# BlancerCarMicrocontrollers.net
KiCad netlist of a schematic drawn in Altium Designer
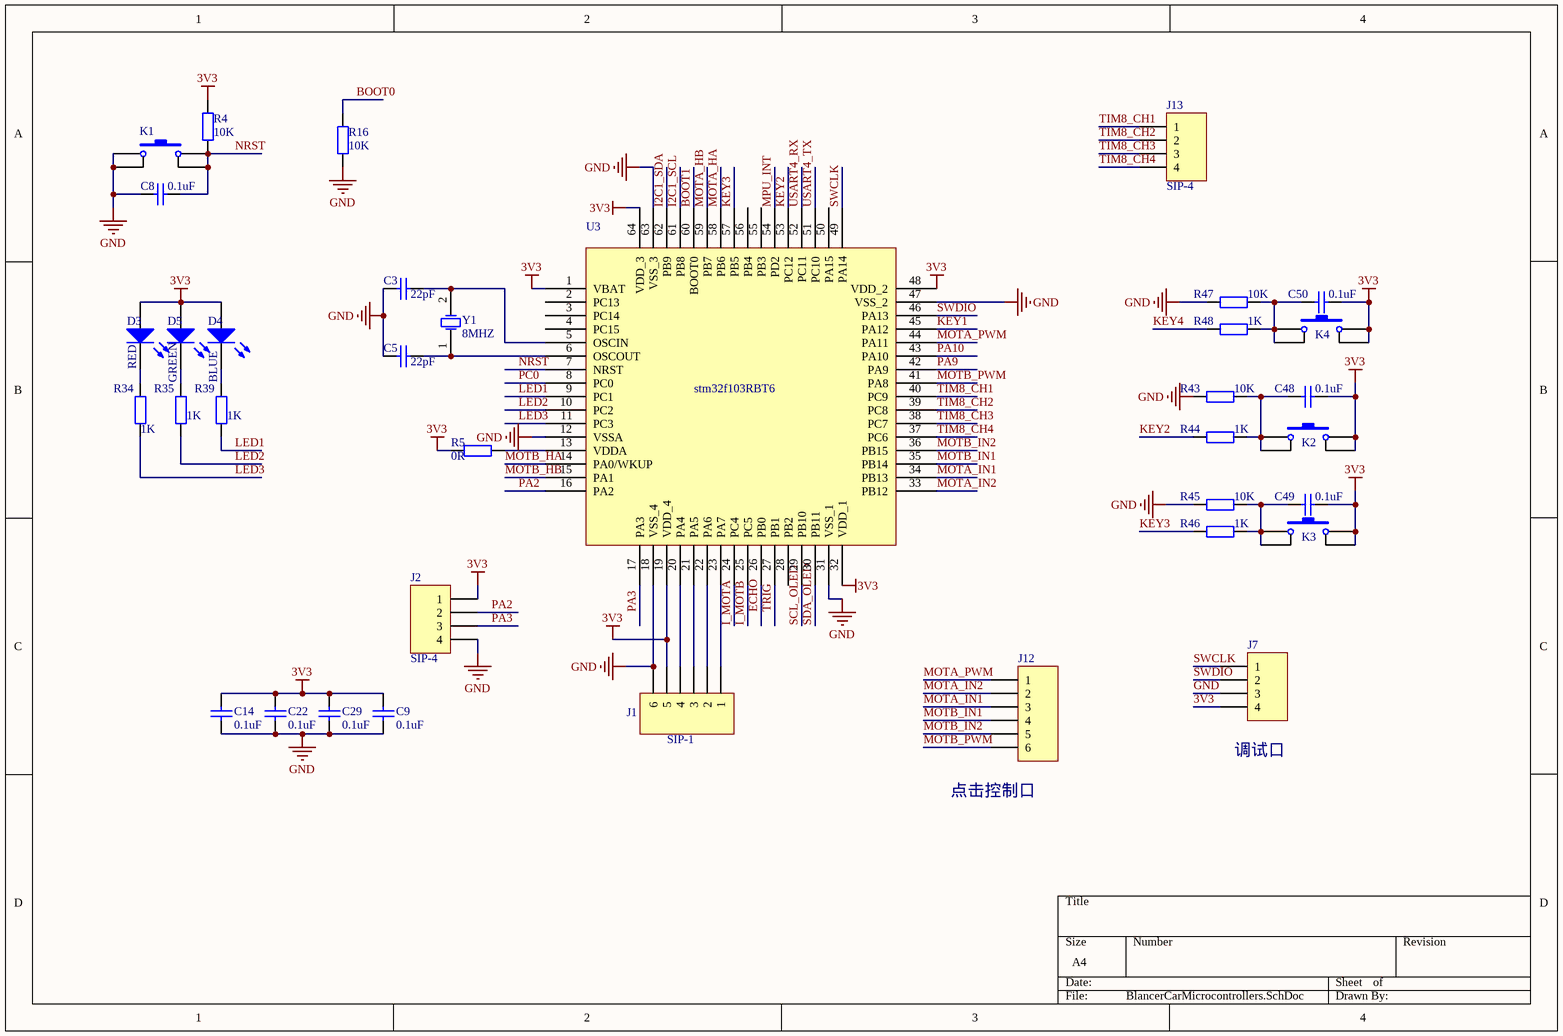
[diagram p0: BlancerCarMicrocontrollers.SchDoc]

(export (version "E")
  (design (tool "Eeschema 10.0.6"))
  (components
    (comp (ref "C3")
      (value "22pF")
      (footprint "0805-1")
      (description "Capacitor")
      (fields (field (name "Comment") "Cap") (field (name "PUBLISHER") "Altium Limited"))
      (libsource (lib "BlancerCar") (part "Cap"))
    )
    (comp (ref "C5")
      (value "22pF")
      (footprint "0805-1")
      (description "Capacitor")
      (fields (field (name "Comment") "Cap") (field (name "PUBLISHER") "Altium Limited"))
      (libsource (lib "BlancerCar") (part "Cap"))
    )
    (comp (ref "C8")
      (value "0.1uF")
      (footprint "0805-1")
      (description "Capacitor")
      (fields (field (name "Comment") "Cap") (field (name "PUBLISHER") "Altium Limited"))
      (libsource (lib "BlancerCar") (part "Cap"))
    )
    (comp (ref "C9")
      (value "0.1uF")
      (footprint "0805-1")
      (description "Capacitor")
      (fields (field (name "Comment") "Cap") (field (name "PUBLISHER") "Altium Limited"))
      (libsource (lib "BlancerCar") (part "Cap"))
    )
    (comp (ref "C14")
      (value "0.1uF")
      (footprint "0805-1")
      (description "Capacitor")
      (fields (field (name "Comment") "Cap") (field (name "PUBLISHER") "Altium Limited"))
      (libsource (lib "BlancerCar") (part "Cap"))
    )
    (comp (ref "C22")
      (value "0.1uF")
      (footprint "0805-1")
      (description "Capacitor")
      (fields (field (name "Comment") "Cap") (field (name "PUBLISHER") "Altium Limited"))
      (libsource (lib "BlancerCar") (part "Cap"))
    )
    (comp (ref "C29")
      (value "0.1uF")
      (footprint "0805-1")
      (description "Capacitor")
      (fields (field (name "Comment") "Cap") (field (name "PUBLISHER") "Altium Limited"))
      (libsource (lib "BlancerCar") (part "Cap"))
    )
    (comp (ref "C48")
      (value "0.1uF")
      (footprint "0805-1")
      (description "Capacitor")
      (fields (field (name "Comment") "Cap") (field (name "PUBLISHER") "Altium Limited"))
      (libsource (lib "BlancerCar") (part "Cap"))
    )
    (comp (ref "C49")
      (value "0.1uF")
      (footprint "0805-1")
      (description "Capacitor")
      (fields (field (name "Comment") "Cap") (field (name "PUBLISHER") "Altium Limited"))
      (libsource (lib "BlancerCar") (part "Cap"))
    )
    (comp (ref "C50")
      (value "0.1uF")
      (footprint "0805-1")
      (description "Capacitor")
      (fields (field (name "Comment") "Cap") (field (name "PUBLISHER") "Altium Limited"))
      (libsource (lib "BlancerCar") (part "Cap"))
    )
    (comp (ref "D3")
      (value "RED")
      (footprint "LED_0805")
      (description "发光二极管")
      (fields (field (name "PUBLISHER") "Altium Limited"))
      (libsource (lib "xdhADL") (part "LED0"))
    )
    (comp (ref "D4")
      (value "BLUE")
      (footprint "LED_0805")
      (description "发光二极管")
      (fields (field (name "PUBLISHER") "Altium Limited"))
      (libsource (lib "xdhADL") (part "LED0"))
    )
    (comp (ref "D5")
      (value "GREEN")
      (footprint "LED_0805")
      (description "发光二极管")
      (fields (field (name "PUBLISHER") "Altium Limited"))
      (libsource (lib "xdhADL") (part "LED0"))
    )
    (comp (ref "J1")
      (value "SIP-1")
      (footprint "HDR1X6")
      (description "Header, 6-Pin")
      (fields (field (name "PUBLISHER") "Altium Limited"))
      (libsource (lib "Miscellaneous Connectors") (part "Header 6"))
    )
    (comp (ref "J2")
      (value "SIP-4")
      (footprint "HDR1X4")
      (description "Header, 4-Pin")
      (fields (field (name "PUBLISHER") "Altium Limited"))
      (libsource (lib "BlancerCar") (part "Header 4"))
    )
    (comp (ref "J7")
      (value "Header 4")
      (footprint "HDR1X4")
      (description "Header, 4-Pin")
      (fields (field (name "PUBLISHER") "Altium Limited"))
      (libsource (lib "Miscellaneous Connectors") (part "Header 4"))
    )
    (comp (ref "J12")
      (value "Header 6")
      (footprint "HDR1X6")
      (description "Header, 6-Pin")
      (fields (field (name "PUBLISHER") "Altium Limited"))
      (libsource (lib "") (part "Header 6_1"))
    )
    (comp (ref "J13")
      (value "SIP-4")
      (footprint "HDR1X4")
      (description "Header, 4-Pin")
      (fields (field (name "PUBLISHER") "Altium Limited"))
      (libsource (lib "Miscellaneous Connectors") (part "Header 4"))
    )
    (comp (ref "K1")
      (value "SW-PB4")
      (footprint "SW_PB4_A1")
      (description "微动开关")
      (fields (field (name "PUBLISHER") "Altium Limited"))
      (libsource (lib "xdhADL") (part "SW-PB4"))
    )
    (comp (ref "K2")
      (value "SW-PB4")
      (footprint "SW_PB4_A1")
      (description "微动开关")
      (fields (field (name "PUBLISHER") "Altium Limited"))
      (libsource (lib "xdhADL") (part "SW-PB4"))
    )
    (comp (ref "K3")
      (value "SW-PB4")
      (footprint "SW_PB4_A1")
      (description "微动开关")
      (fields (field (name "PUBLISHER") "Altium Limited"))
      (libsource (lib "xdhADL") (part "SW-PB4"))
    )
    (comp (ref "K4")
      (value "SW-PB4")
      (footprint "SW_PB4_A1")
      (description "微动开关")
      (fields (field (name "PUBLISHER") "Altium Limited"))
      (libsource (lib "xdhADL") (part "SW-PB4"))
    )
    (comp (ref "R4")
      (value "10K")
      (footprint "0805-1")
      (description "贴片电阻")
      (fields (field (name "Comment") "Res1") (field (name "PUBLISHER") "Altium Limited"))
      (libsource (lib "") (part "Res1_2"))
    )
    (comp (ref "R5")
      (value "0R")
      (footprint "0805-1")
      (description "贴片电阻")
      (fields (field (name "Comment") "Res1") (field (name "PUBLISHER") "Altium Limited"))
      (libsource (lib "") (part "Res1_1"))
    )
    (comp (ref "R16")
      (value "10K")
      (footprint "0805-1")
      (description "贴片电阻")
      (fields (field (name "Comment") "Res1") (field (name "PUBLISHER") "Altium Limited"))
      (libsource (lib "xdhADL") (part "Res1"))
    )
    (comp (ref "R34")
      (value "1K")
      (footprint "0805-1")
      (description "贴片电阻")
      (fields (field (name "Comment") "Res1") (field (name "PUBLISHER") "Altium Limited"))
      (libsource (lib "xdhADL") (part "Res1"))
    )
    (comp (ref "R35")
      (value "1K")
      (footprint "0805-1")
      (description "贴片电阻")
      (fields (field (name "Comment") "Res1") (field (name "PUBLISHER") "Altium Limited"))
      (libsource (lib "xdhADL") (part "Res1"))
    )
    (comp (ref "R39")
      (value "1K")
      (footprint "0805-1")
      (description "贴片电阻")
      (fields (field (name "Comment") "Res1") (field (name "PUBLISHER") "Altium Limited"))
      (libsource (lib "xdhADL") (part "Res1"))
    )
    (comp (ref "R43")
      (value "10K")
      (footprint "0805-1")
      (description "贴片电阻")
      (fields (field (name "Comment") "Res1") (field (name "PUBLISHER") "Altium Limited"))
      (libsource (lib "") (part "Res1_1"))
    )
    (comp (ref "R44")
      (value "1K")
      (footprint "0805-1")
      (description "贴片电阻")
      (fields (field (name "Comment") "Res1") (field (name "PUBLISHER") "Altium Limited"))
      (libsource (lib "") (part "Res1_1"))
    )
    (comp (ref "R45")
      (value "10K")
      (footprint "0805-1")
      (description "贴片电阻")
      (fields (field (name "Comment") "Res1") (field (name "PUBLISHER") "Altium Limited"))
      (libsource (lib "") (part "Res1_1"))
    )
    (comp (ref "R46")
      (value "1K")
      (footprint "0805-1")
      (description "贴片电阻")
      (fields (field (name "Comment") "Res1") (field (name "PUBLISHER") "Altium Limited"))
      (libsource (lib "") (part "Res1_1"))
    )
    (comp (ref "R47")
      (value "10K")
      (footprint "0805-1")
      (description "贴片电阻")
      (fields (field (name "Comment") "Res1") (field (name "PUBLISHER") "Altium Limited"))
      (libsource (lib "") (part "Res1_1"))
    )
    (comp (ref "R48")
      (value "1K")
      (footprint "0805-1")
      (description "贴片电阻")
      (fields (field (name "Comment") "Res1") (field (name "PUBLISHER") "Altium Limited"))
      (libsource (lib "") (part "Res1_1"))
    )
    (comp (ref "U3")
      (value "stm32f103RBT6")
      (footprint "STM32F103RBT6(LQFP-64)")
      (libsource (lib "xdhADL") (part "stm32f103RBT6"))
    )
    (comp (ref "Y1")
      (value "8MHZ")
      (footprint "晶振 8M")
      (description "Crystal Oscillator")
      (fields (field (name "PUBLISHER") "Altium Limited"))
      (libsource (lib "BlancerCar") (part "XTAL"))
    )
  )
  (nets
    (net (code "1") (name "/BOOT0") (class "Default")
      (node (ref "R16") (pin "2") (pinfunction "2_2") (pintype "passive"))
    )
    (net (code "2") (name "/BOOT1") (class "Default")
      (node (ref "U3") (pin "60") (pinfunction "BOOT0_60") (pintype "passive"))
    )
    (net (code "3") (name "/ECHO") (class "Default")
      (node (ref "U3") (pin "26") (pinfunction "PB0_26") (pintype "passive"))
    )
    (net (code "4") (name "/I2C1_SCL") (class "Default")
      (node (ref "U3") (pin "61") (pinfunction "PB8_61") (pintype "passive"))
    )
    (net (code "5") (name "/I2C1_SDA") (class "Default")
      (node (ref "U3") (pin "62") (pinfunction "PB9_62") (pintype "passive"))
    )
    (net (code "6") (name "/I_MOTA") (class "Default")
      (node (ref "U3") (pin "24") (pinfunction "PC4_24") (pintype "passive"))
    )
    (net (code "7") (name "/I_MOTB") (class "Default")
      (node (ref "U3") (pin "25") (pinfunction "PC5_25") (pintype "passive"))
    )
    (net (code "8") (name "/KEY1") (class "Default")
      (node (ref "U3") (pin "45") (pinfunction "PA12_45") (pintype "passive"))
    )
    (net (code "9") (name "/KEY2") (class "Default")
      (node (ref "R44") (pin "1") (pinfunction "1_1") (pintype "passive"))
      (node (ref "U3") (pin "53") (pinfunction "PC12_53") (pintype "passive"))
    )
    (net (code "10") (name "/KEY3") (class "Default")
      (node (ref "R46") (pin "1") (pinfunction "1_1") (pintype "passive"))
      (node (ref "U3") (pin "57") (pinfunction "PB5_57") (pintype "passive"))
    )
    (net (code "11") (name "/KEY4") (class "Default")
      (node (ref "R48") (pin "1") (pinfunction "1_1") (pintype "passive"))
    )
    (net (code "12") (name "/LED1") (class "Default")
      (node (ref "R39") (pin "1") (pinfunction "1_1") (pintype "passive"))
      (node (ref "U3") (pin "9") (pinfunction "PC1_9") (pintype "passive"))
    )
    (net (code "13") (name "/LED2") (class "Default")
      (node (ref "R35") (pin "1") (pinfunction "1_1") (pintype "passive"))
      (node (ref "U3") (pin "10") (pinfunction "PC2_10") (pintype "passive"))
    )
    (net (code "14") (name "/LED3") (class "Default")
      (node (ref "R34") (pin "1") (pinfunction "1_1") (pintype "passive"))
      (node (ref "U3") (pin "11") (pinfunction "PC3_11") (pintype "passive"))
    )
    (net (code "15") (name "/MOTA_HA") (class "Default")
      (node (ref "U3") (pin "58") (pinfunction "PB6_58") (pintype "passive"))
    )
    (net (code "16") (name "/MOTA_HB") (class "Default")
      (node (ref "U3") (pin "59") (pinfunction "PB7_59") (pintype "passive"))
    )
    (net (code "17") (name "/MOTA_IN1") (class "Default")
      (node (ref "J12") (pin "3") (pinfunction "3_3") (pintype "passive"))
      (node (ref "U3") (pin "34") (pinfunction "PB13_34") (pintype "passive"))
    )
    (net (code "18") (name "/MOTA_IN2") (class "Default")
      (node (ref "J12") (pin "2") (pinfunction "2_2") (pintype "passive"))
      (node (ref "U3") (pin "33") (pinfunction "PB12_33") (pintype "passive"))
    )
    (net (code "19") (name "/MOTA_PWM") (class "Default")
      (node (ref "J12") (pin "1") (pinfunction "1_1") (pintype "passive"))
      (node (ref "U3") (pin "44") (pinfunction "PA11_44") (pintype "passive"))
    )
    (net (code "20") (name "/MOTB_HA") (class "Default")
      (node (ref "U3") (pin "14") (pinfunction "PA0/WKUP_14") (pintype "passive"))
    )
    (net (code "21") (name "/MOTB_HB") (class "Default")
      (node (ref "U3") (pin "15") (pinfunction "PA1_15") (pintype "passive"))
    )
    (net (code "22") (name "/MOTB_IN1") (class "Default")
      (node (ref "J12") (pin "4") (pinfunction "4_4") (pintype "passive"))
      (node (ref "U3") (pin "35") (pinfunction "PB14_35") (pintype "passive"))
    )
    (net (code "23") (name "/MOTB_IN2") (class "Default")
      (node (ref "J12") (pin "5") (pinfunction "5_5") (pintype "passive"))
      (node (ref "U3") (pin "36") (pinfunction "PB15_36") (pintype "passive"))
    )
    (net (code "24") (name "/MOTB_PWM") (class "Default")
      (node (ref "J12") (pin "6") (pinfunction "6_6") (pintype "passive"))
      (node (ref "U3") (pin "41") (pinfunction "PA8_41") (pintype "passive"))
    )
    (net (code "25") (name "/MPU_INT") (class "Default")
      (node (ref "U3") (pin "54") (pinfunction "PD2_54") (pintype "passive"))
    )
    (net (code "26") (name "/NRST") (class "Default")
      (node (ref "C8") (pin "2") (pinfunction "2_2") (pintype "passive"))
      (node (ref "K1") (pin "2") (pinfunction "2_2") (pintype "passive"))
      (node (ref "K1") (pin "3") (pinfunction "3_3") (pintype "passive"))
      (node (ref "R4") (pin "2") (pinfunction "2_2") (pintype "passive"))
      (node (ref "U3") (pin "7") (pinfunction "NRST_7") (pintype "passive"))
    )
    (net (code "27") (name "/PA2") (class "Default")
      (node (ref "J2") (pin "2") (pinfunction "2_2") (pintype "passive"))
      (node (ref "U3") (pin "16") (pinfunction "PA2_16") (pintype "passive"))
    )
    (net (code "28") (name "/PA3") (class "Default")
      (node (ref "J2") (pin "3") (pinfunction "3_3") (pintype "passive"))
      (node (ref "U3") (pin "17") (pinfunction "PA3_17") (pintype "passive"))
    )
    (net (code "29") (name "/PA9") (class "Default")
      (node (ref "U3") (pin "42") (pinfunction "PA9_42") (pintype "passive"))
    )
    (net (code "30") (name "/PA10") (class "Default")
      (node (ref "U3") (pin "43") (pinfunction "PA10_43") (pintype "passive"))
    )
    (net (code "31") (name "/PC0") (class "Default")
      (node (ref "U3") (pin "8") (pinfunction "PC0_8") (pintype "passive"))
    )
    (net (code "32") (name "/SCL_OLED") (class "Default")
      (node (ref "U3") (pin "29") (pinfunction "PB10_29") (pintype "passive"))
    )
    (net (code "33") (name "/SDA_OLED") (class "Default")
      (node (ref "U3") (pin "30") (pinfunction "PB11_30") (pintype "passive"))
    )
    (net (code "34") (name "/SWCLK") (class "Default")
      (node (ref "J7") (pin "1") (pinfunction "1_1") (pintype "passive"))
      (node (ref "U3") (pin "49") (pinfunction "PA14_49") (pintype "passive"))
    )
    (net (code "35") (name "/SWDIO") (class "Default")
      (node (ref "J7") (pin "2") (pinfunction "2_2") (pintype "passive"))
      (node (ref "U3") (pin "46") (pinfunction "PA13_46") (pintype "passive"))
    )
    (net (code "36") (name "/TIM8_CH1") (class "Default")
      (node (ref "J13") (pin "1") (pinfunction "1_1") (pintype "passive"))
      (node (ref "U3") (pin "40") (pinfunction "PC9_40") (pintype "passive"))
    )
    (net (code "37") (name "/TIM8_CH2") (class "Default")
      (node (ref "J13") (pin "2") (pinfunction "2_2") (pintype "passive"))
      (node (ref "U3") (pin "39") (pinfunction "PC8_39") (pintype "passive"))
    )
    (net (code "38") (name "/TIM8_CH3") (class "Default")
      (node (ref "J13") (pin "3") (pinfunction "3_3") (pintype "passive"))
      (node (ref "U3") (pin "38") (pinfunction "PC7_38") (pintype "passive"))
    )
    (net (code "39") (name "/TIM8_CH4") (class "Default")
      (node (ref "J13") (pin "4") (pinfunction "4_4") (pintype "passive"))
      (node (ref "U3") (pin "37") (pinfunction "PC6_37") (pintype "passive"))
    )
    (net (code "40") (name "/TRIG") (class "Default")
      (node (ref "U3") (pin "27") (pinfunction "PB1_27") (pintype "passive"))
    )
    (net (code "41") (name "/USART4_RX") (class "Default")
      (node (ref "U3") (pin "52") (pinfunction "PC11_52") (pintype "passive"))
    )
    (net (code "42") (name "/USART4_TX") (class "Default")
      (node (ref "U3") (pin "51") (pinfunction "PC10_51") (pintype "passive"))
    )
    (net (code "43") (name "3V3") (class "Default")
      (node (ref "C14") (pin "2") (pinfunction "2_2") (pintype "passive"))
      (node (ref "C22") (pin "2") (pinfunction "2_2") (pintype "passive"))
      (node (ref "C29") (pin "2") (pinfunction "2_2") (pintype "passive"))
      (node (ref "C48") (pin "2") (pinfunction "2_2") (pintype "passive"))
      (node (ref "C49") (pin "2") (pinfunction "2_2") (pintype "passive"))
      (node (ref "C50") (pin "2") (pinfunction "2_2") (pintype "passive"))
      (node (ref "C9") (pin "2") (pinfunction "2_2") (pintype "passive"))
      (node (ref "D3") (pin "1") (pinfunction "A_1") (pintype "passive"))
      (node (ref "D4") (pin "1") (pinfunction "A_1") (pintype "passive"))
      (node (ref "D5") (pin "1") (pinfunction "A_1") (pintype "passive"))
      (node (ref "J1") (pin "5") (pinfunction "5_5") (pintype "passive"))
      (node (ref "J2") (pin "1") (pinfunction "1_1") (pintype "passive"))
      (node (ref "J7") (pin "4") (pinfunction "4_4") (pintype "passive"))
      (node (ref "K2") (pin "2") (pinfunction "2_2") (pintype "passive"))
      (node (ref "K2") (pin "3") (pinfunction "3_3") (pintype "passive"))
      (node (ref "K3") (pin "2") (pinfunction "2_2") (pintype "passive"))
      (node (ref "K3") (pin "3") (pinfunction "3_3") (pintype "passive"))
      (node (ref "K4") (pin "2") (pinfunction "2_2") (pintype "passive"))
      (node (ref "K4") (pin "3") (pinfunction "3_3") (pintype "passive"))
      (node (ref "R4") (pin "1") (pinfunction "1_1") (pintype "passive"))
      (node (ref "R5") (pin "1") (pinfunction "1_1") (pintype "passive"))
      (node (ref "U3") (pin "1") (pinfunction "VBAT_1") (pintype "passive"))
      (node (ref "U3") (pin "19") (pinfunction "VDD_4_19") (pintype "passive"))
      (node (ref "U3") (pin "32") (pinfunction "VDD_1_32") (pintype "passive"))
      (node (ref "U3") (pin "48") (pinfunction "VDD_2_48") (pintype "passive"))
      (node (ref "U3") (pin "64") (pinfunction "VDD_3_64") (pintype "passive"))
    )
    (net (code "44") (name "GND") (class "Default")
      (node (ref "C14") (pin "1") (pinfunction "1_1") (pintype "passive"))
      (node (ref "C22") (pin "1") (pinfunction "1_1") (pintype "passive"))
      (node (ref "C29") (pin "1") (pinfunction "1_1") (pintype "passive"))
      (node (ref "C3") (pin "1") (pinfunction "1_1") (pintype "passive"))
      (node (ref "C5") (pin "1") (pinfunction "1_1") (pintype "passive"))
      (node (ref "C8") (pin "1") (pinfunction "1_1") (pintype "passive"))
      (node (ref "C9") (pin "1") (pinfunction "1_1") (pintype "passive"))
      (node (ref "J1") (pin "6") (pinfunction "6_6") (pintype "passive"))
      (node (ref "J2") (pin "4") (pinfunction "4_4") (pintype "passive"))
      (node (ref "J7") (pin "3") (pinfunction "3_3") (pintype "passive"))
      (node (ref "K1") (pin "1") (pinfunction "1_1") (pintype "passive"))
      (node (ref "K1") (pin "4") (pinfunction "4_4") (pintype "passive"))
      (node (ref "R16") (pin "1") (pinfunction "1_1") (pintype "passive"))
      (node (ref "R43") (pin "1") (pinfunction "1_1") (pintype "passive"))
      (node (ref "R45") (pin "1") (pinfunction "1_1") (pintype "passive"))
      (node (ref "R47") (pin "1") (pinfunction "1_1") (pintype "passive"))
      (node (ref "U3") (pin "12") (pinfunction "VSSA_12") (pintype "passive"))
      (node (ref "U3") (pin "18") (pinfunction "VSS_4_18") (pintype "passive"))
      (node (ref "U3") (pin "31") (pinfunction "VSS_1_31") (pintype "passive"))
      (node (ref "U3") (pin "47") (pinfunction "VSS_2_47") (pintype "passive"))
      (node (ref "U3") (pin "63") (pinfunction "VSS_3_63") (pintype "passive"))
    )
    (net (code "45") (name "Net-(C48-Pad1)") (class "Default")
      (node (ref "C48") (pin "1") (pinfunction "1_1") (pintype "passive"))
      (node (ref "K2") (pin "1") (pinfunction "1_1") (pintype "passive"))
      (node (ref "K2") (pin "4") (pinfunction "4_4") (pintype "passive"))
      (node (ref "R43") (pin "2") (pinfunction "2_2") (pintype "passive"))
      (node (ref "R44") (pin "2") (pinfunction "2_2") (pintype "passive"))
    )
    (net (code "46") (name "Net-(C49-Pad1)") (class "Default")
      (node (ref "C49") (pin "1") (pinfunction "1_1") (pintype "passive"))
      (node (ref "K3") (pin "1") (pinfunction "1_1") (pintype "passive"))
      (node (ref "K3") (pin "4") (pinfunction "4_4") (pintype "passive"))
      (node (ref "R45") (pin "2") (pinfunction "2_2") (pintype "passive"))
      (node (ref "R46") (pin "2") (pinfunction "2_2") (pintype "passive"))
    )
    (net (code "47") (name "Net-(C50-Pad1)") (class "Default")
      (node (ref "C50") (pin "1") (pinfunction "1_1") (pintype "passive"))
      (node (ref "K4") (pin "1") (pinfunction "1_1") (pintype "passive"))
      (node (ref "K4") (pin "4") (pinfunction "4_4") (pintype "passive"))
      (node (ref "R47") (pin "2") (pinfunction "2_2") (pintype "passive"))
      (node (ref "R48") (pin "2") (pinfunction "2_2") (pintype "passive"))
    )
    (net (code "48") (name "Net-(D3-K)") (class "Default")
      (node (ref "D3") (pin "2") (pinfunction "K_2") (pintype "passive"))
      (node (ref "R34") (pin "2") (pinfunction "2_2") (pintype "passive"))
    )
    (net (code "49") (name "Net-(D4-K)") (class "Default")
      (node (ref "D4") (pin "2") (pinfunction "K_2") (pintype "passive"))
      (node (ref "R39") (pin "2") (pinfunction "2_2") (pintype "passive"))
    )
    (net (code "50") (name "Net-(D5-K)") (class "Default")
      (node (ref "D5") (pin "2") (pinfunction "K_2") (pintype "passive"))
      (node (ref "R35") (pin "2") (pinfunction "2_2") (pintype "passive"))
    )
    (net (code "51") (name "Net-(U3-OSCIN)") (class "Default")
      (node (ref "C3") (pin "2") (pinfunction "2_2") (pintype "passive"))
      (node (ref "U3") (pin "5") (pinfunction "OSCIN_5") (pintype "passive"))
      (node (ref "Y1") (pin "2") (pinfunction "OSC2_2") (pintype "passive"))
    )
    (net (code "52") (name "Net-(U3-OSCOUT)") (class "Default")
      (node (ref "C5") (pin "2") (pinfunction "2_2") (pintype "passive"))
      (node (ref "U3") (pin "6") (pinfunction "OSCOUT_6") (pintype "passive"))
      (node (ref "Y1") (pin "1") (pinfunction "OSC1_1") (pintype "passive"))
    )
    (net (code "53") (name "Net-(U3-PA4)") (class "Default")
      (node (ref "J1") (pin "4") (pinfunction "4_4") (pintype "passive"))
      (node (ref "U3") (pin "20") (pinfunction "PA4_20") (pintype "passive"))
    )
    (net (code "54") (name "Net-(U3-PA5)") (class "Default")
      (node (ref "J1") (pin "3") (pinfunction "3_3") (pintype "passive"))
      (node (ref "U3") (pin "21") (pinfunction "PA5_21") (pintype "passive"))
    )
    (net (code "55") (name "Net-(U3-PA6)") (class "Default")
      (node (ref "J1") (pin "2") (pinfunction "2_2") (pintype "passive"))
      (node (ref "U3") (pin "22") (pinfunction "PA6_22") (pintype "passive"))
    )
    (net (code "56") (name "Net-(U3-PA7)") (class "Default")
      (node (ref "J1") (pin "1") (pinfunction "1_1") (pintype "passive"))
      (node (ref "U3") (pin "23") (pinfunction "PA7_23") (pintype "passive"))
    )
    (net (code "57") (name "Net-(U3-VDDA)") (class "Default")
      (node (ref "R5") (pin "2") (pinfunction "2_2") (pintype "passive"))
      (node (ref "U3") (pin "13") (pinfunction "VDDA_13") (pintype "passive"))
    )
    (net (code "58") (name "unconnected-(U3-PA15-Pad50)") (class "Default")
      (node (ref "U3") (pin "50") (pinfunction "PA15_50") (pintype "passive"))
    )
    (net (code "59") (name "unconnected-(U3-PB2-Pad28)") (class "Default")
      (node (ref "U3") (pin "28") (pinfunction "PB2_28") (pintype "passive"))
    )
    (net (code "60") (name "unconnected-(U3-PB3-Pad55)") (class "Default")
      (node (ref "U3") (pin "55") (pinfunction "PB3_55") (pintype "passive"))
    )
    (net (code "61") (name "unconnected-(U3-PB4-Pad56)") (class "Default")
      (node (ref "U3") (pin "56") (pinfunction "PB4_56") (pintype "passive"))
    )
    (net (code "62") (name "unconnected-(U3-PC13-Pad2)") (class "Default")
      (node (ref "U3") (pin "2") (pinfunction "PC13_2") (pintype "passive"))
    )
    (net (code "63") (name "unconnected-(U3-PC14-Pad3)") (class "Default")
      (node (ref "U3") (pin "3") (pinfunction "PC14_3") (pintype "passive"))
    )
    (net (code "64") (name "unconnected-(U3-PC15-Pad4)") (class "Default")
      (node (ref "U3") (pin "4") (pinfunction "PC15_4") (pintype "passive"))
    )
  )
)
